# 4-pin_SOT-89_SOT-223.net
KiCad netlist of a schematic drawn in EAGLE
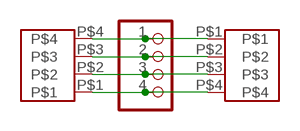
[diagram p0: schematic, sheet 1]

(export (version "E")
  (design (tool "Eeschema 10.0.6"))
  (components
    (comp (ref "JP1")
      (value "PADS-4")
      (footprint "eagle-import:PADS-4")
      (libsource (lib "eagle-import") (part "PADS-4"))
    )
    (comp (ref "U$1")
      (value "SOT89")
      (footprint "eagle-import:SOT89")
      (libsource (lib "eagle-import") (part "SOT89"))
    )
    (comp (ref "U$2")
      (value "SOT223")
      (footprint "eagle-import:SOT223")
      (libsource (lib "eagle-import") (part "SOT223"))
    )
  )
  (nets
    (net (code "1") (name "Net-(JP1-Pad1)") (class "Default")
      (node (ref "JP1") (pin "1") (pinfunction "1_1") (pintype "passive"))
      (node (ref "U$1") (pin "P$1") (pinfunction "P$1_P$1") (pintype "bidirectional"))
      (node (ref "U$2") (pin "P$4") (pinfunction "P$4_P$4") (pintype "bidirectional"))
    )
    (net (code "2") (name "Net-(JP1-Pad2)") (class "Default")
      (node (ref "JP1") (pin "2") (pinfunction "2_2") (pintype "passive"))
      (node (ref "U$1") (pin "P$2") (pinfunction "P$2_P$2") (pintype "bidirectional"))
      (node (ref "U$2") (pin "P$3") (pinfunction "P$3_P$3") (pintype "bidirectional"))
    )
    (net (code "3") (name "Net-(JP1-Pad3)") (class "Default")
      (node (ref "JP1") (pin "3") (pinfunction "3_3") (pintype "passive"))
      (node (ref "U$1") (pin "P$3") (pinfunction "P$3_P$3") (pintype "bidirectional"))
      (node (ref "U$2") (pin "P$2") (pinfunction "P$2_P$2") (pintype "bidirectional"))
    )
    (net (code "4") (name "Net-(JP1-Pad4)") (class "Default")
      (node (ref "JP1") (pin "4") (pinfunction "4_4") (pintype "passive"))
      (node (ref "U$1") (pin "P$4") (pinfunction "P$4_P$4") (pintype "bidirectional"))
      (node (ref "U$2") (pin "P$1") (pinfunction "P$1_P$1") (pintype "bidirectional"))
    )
  )
)
